# l298.net
KiCad netlist of a schematic drawn in EAGLE
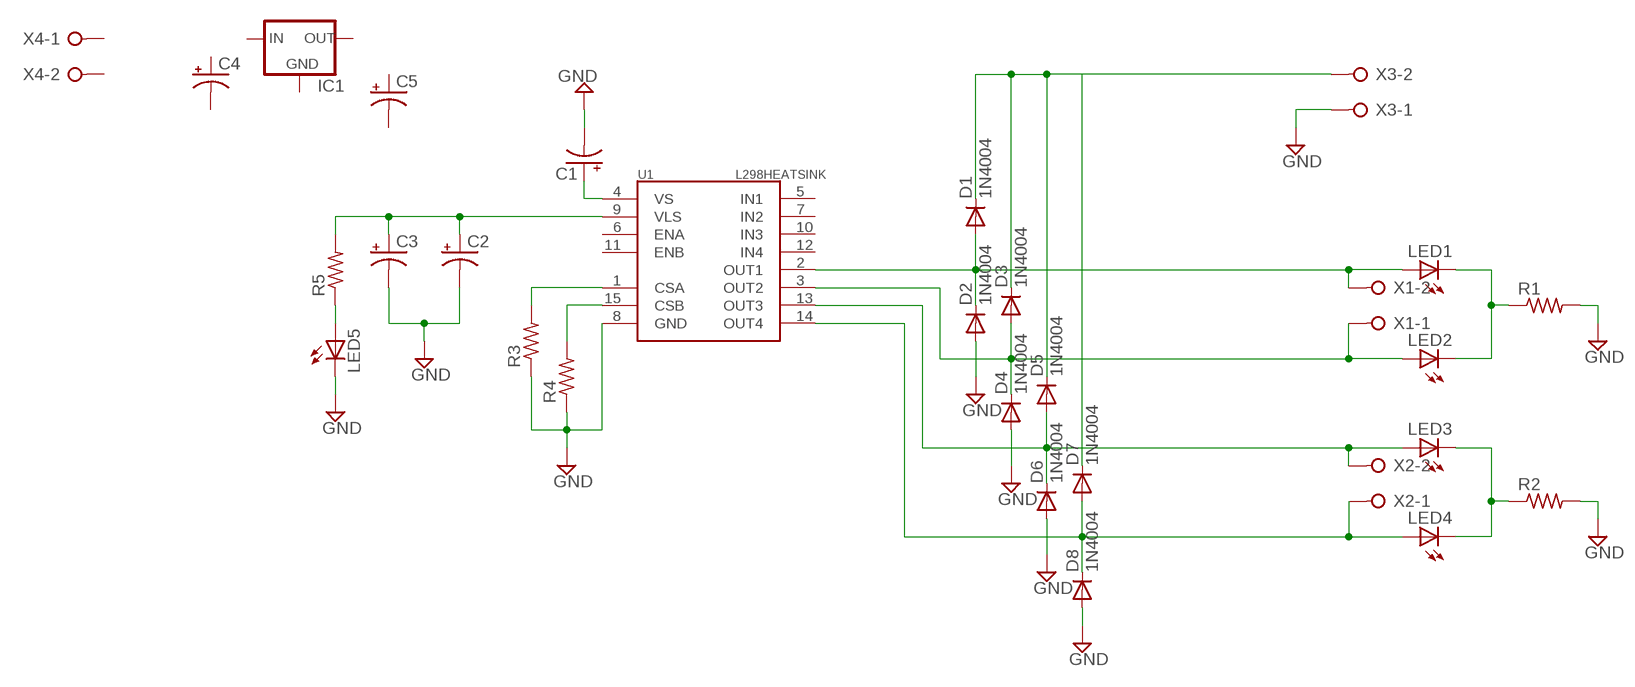
[diagram p0: schematic, sheet 1]

(export (version "E")
  (design (tool "Eeschema 10.0.6"))
  (components
    (comp (ref "C1")
      (value "CPOL-USE3.5-8")
      (footprint "eagle-import:E3,5-8")
      (libsource (lib "eagle-import") (part "CPOL-USE3.5-8"))
    )
    (comp (ref "C2")
      (value "CPOL-USE3.5-8")
      (footprint "eagle-import:E3,5-8")
      (libsource (lib "eagle-import") (part "CPOL-USE3.5-8"))
    )
    (comp (ref "C3")
      (value "CPOL-USE3.5-8")
      (footprint "eagle-import:E3,5-8")
      (libsource (lib "eagle-import") (part "CPOL-USE3.5-8"))
    )
    (comp (ref "C4")
      (value "CPOL-USE3.5-8")
      (footprint "eagle-import:E3,5-8")
      (libsource (lib "eagle-import") (part "CPOL-USE3.5-8"))
    )
    (comp (ref "C5")
      (value "CPOL-USE3.5-8")
      (footprint "eagle-import:E3,5-8")
      (libsource (lib "eagle-import") (part "CPOL-USE3.5-8"))
    )
    (comp (ref "D1")
      (value "1N4004")
      (footprint "eagle-import:DO41-10")
      (libsource (lib "eagle-import") (part "1N4004"))
    )
    (comp (ref "D2")
      (value "1N4004")
      (footprint "eagle-import:DO41-10")
      (libsource (lib "eagle-import") (part "1N4004"))
    )
    (comp (ref "D3")
      (value "1N4004")
      (footprint "eagle-import:DO41-10")
      (libsource (lib "eagle-import") (part "1N4004"))
    )
    (comp (ref "D4")
      (value "1N4004")
      (footprint "eagle-import:DO41-10")
      (libsource (lib "eagle-import") (part "1N4004"))
    )
    (comp (ref "D5")
      (value "1N4004")
      (footprint "eagle-import:DO41-10")
      (libsource (lib "eagle-import") (part "1N4004"))
    )
    (comp (ref "D6")
      (value "1N4004")
      (footprint "eagle-import:DO41-10")
      (libsource (lib "eagle-import") (part "1N4004"))
    )
    (comp (ref "D7")
      (value "1N4004")
      (footprint "eagle-import:DO41-10")
      (libsource (lib "eagle-import") (part "1N4004"))
    )
    (comp (ref "D8")
      (value "1N4004")
      (footprint "eagle-import:DO41-10")
      (libsource (lib "eagle-import") (part "1N4004"))
    )
    (comp (ref "IC1")
      (value "V_REG_78XXSIDE")
      (footprint "eagle-import:78XXL")
      (libsource (lib "eagle-import") (part "V_REG_78XXSIDE"))
    )
    (comp (ref "LED1")
      (value "LED5MM")
      (footprint "eagle-import:LED5MM")
      (libsource (lib "eagle-import") (part "LED5MM"))
    )
    (comp (ref "LED2")
      (value "LED5MM")
      (footprint "eagle-import:LED5MM")
      (libsource (lib "eagle-import") (part "LED5MM"))
    )
    (comp (ref "LED3")
      (value "LED5MM")
      (footprint "eagle-import:LED5MM")
      (libsource (lib "eagle-import") (part "LED5MM"))
    )
    (comp (ref "LED4")
      (value "LED5MM")
      (footprint "eagle-import:LED5MM")
      (libsource (lib "eagle-import") (part "LED5MM"))
    )
    (comp (ref "LED5")
      (value "LED5MM")
      (footprint "eagle-import:LED5MM")
      (libsource (lib "eagle-import") (part "LED5MM"))
    )
    (comp (ref "R1")
      (value "R-US_0207/10")
      (footprint "eagle-import:0207_10")
      (libsource (lib "eagle-import") (part "R-US_0207/10"))
    )
    (comp (ref "R2")
      (value "R-US_0207/10")
      (footprint "eagle-import:0207_10")
      (libsource (lib "eagle-import") (part "R-US_0207/10"))
    )
    (comp (ref "R3")
      (value "R-US_0207/10")
      (footprint "eagle-import:0207_10")
      (libsource (lib "eagle-import") (part "R-US_0207/10"))
    )
    (comp (ref "R4")
      (value "R-US_0207/10")
      (footprint "eagle-import:0207_10")
      (libsource (lib "eagle-import") (part "R-US_0207/10"))
    )
    (comp (ref "R5")
      (value "R-US_0207/10")
      (footprint "eagle-import:0207_10")
      (libsource (lib "eagle-import") (part "R-US_0207/10"))
    )
    (comp (ref "U1")
      (value "L298HEATSINK")
      (footprint "eagle-import:MULTIWATT15_6400BGHEATSINK")
      (libsource (lib "eagle-import") (part "L298HEATSINK"))
    )
    (comp (ref "X1")
      (value "W237-2N")
      (footprint "eagle-import:W237-2N")
      (libsource (lib "eagle-import") (part "W237-2N"))
    )
    (comp (ref "X2")
      (value "W237-2N")
      (footprint "eagle-import:W237-2N")
      (libsource (lib "eagle-import") (part "W237-2N"))
    )
    (comp (ref "X3")
      (value "W237-2N")
      (footprint "eagle-import:W237-2N")
      (libsource (lib "eagle-import") (part "W237-2N"))
    )
    (comp (ref "X4")
      (value "W237-2N")
      (footprint "eagle-import:W237-2N")
      (libsource (lib "eagle-import") (part "W237-2N"))
    )
  )
  (nets
    (net (code "1") (name "GND") (class "Default")
      (node (ref "C1") (pin "-") (pinfunction "-_-") (pintype "passive"))
      (node (ref "C2") (pin "-") (pinfunction "-_-") (pintype "passive"))
      (node (ref "C3") (pin "-") (pinfunction "-_-") (pintype "passive"))
      (node (ref "D2") (pin "A") (pinfunction "A_A") (pintype "passive"))
      (node (ref "D4") (pin "A") (pinfunction "A_A") (pintype "passive"))
      (node (ref "D6") (pin "A") (pinfunction "A_A") (pintype "passive"))
      (node (ref "D8") (pin "A") (pinfunction "A_A") (pintype "passive"))
      (node (ref "LED5") (pin "K") (pinfunction "C_K") (pintype "passive"))
      (node (ref "R1") (pin "2") (pinfunction "2_2") (pintype "passive"))
      (node (ref "R2") (pin "2") (pinfunction "2_2") (pintype "passive"))
      (node (ref "R3") (pin "1") (pinfunction "1_1") (pintype "passive"))
      (node (ref "R4") (pin "1") (pinfunction "1_1") (pintype "passive"))
      (node (ref "U1") (pin "8") (pinfunction "GND_8") (pintype "bidirectional"))
      (node (ref "X3") (pin "1") (pinfunction "KL_1") (pintype "passive"))
    )
    (net (code "2") (name "Net-(LED1-C)") (class "Default")
      (node (ref "LED1") (pin "K") (pinfunction "C_K") (pintype "passive"))
      (node (ref "LED2") (pin "K") (pinfunction "C_K") (pintype "passive"))
      (node (ref "R1") (pin "1") (pinfunction "1_1") (pintype "passive"))
    )
    (net (code "3") (name "Net-(LED3-C)") (class "Default")
      (node (ref "LED3") (pin "K") (pinfunction "C_K") (pintype "passive"))
      (node (ref "LED4") (pin "K") (pinfunction "C_K") (pintype "passive"))
      (node (ref "R2") (pin "1") (pinfunction "1_1") (pintype "passive"))
    )
    (net (code "4") (name "Net-(LED5-PadA)") (class "Default")
      (node (ref "LED5") (pin "A") (pinfunction "A_A") (pintype "passive"))
      (node (ref "R5") (pin "1") (pinfunction "1_1") (pintype "passive"))
    )
    (net (code "5") (name "Net-(U1-CSA)") (class "Default")
      (node (ref "R3") (pin "2") (pinfunction "2_2") (pintype "passive"))
      (node (ref "U1") (pin "1") (pinfunction "CSA_1") (pintype "bidirectional"))
    )
    (net (code "6") (name "Net-(U1-CSB)") (class "Default")
      (node (ref "R4") (pin "2") (pinfunction "2_2") (pintype "passive"))
      (node (ref "U1") (pin "15") (pinfunction "CSB_15") (pintype "bidirectional"))
    )
    (net (code "7") (name "Net-(U1-OUT1)") (class "Default")
      (node (ref "D1") (pin "A") (pinfunction "A_A") (pintype "passive"))
      (node (ref "D2") (pin "C") (pinfunction "C_C") (pintype "passive"))
      (node (ref "LED1") (pin "A") (pinfunction "A_A") (pintype "passive"))
      (node (ref "U1") (pin "2") (pinfunction "OUT1_2") (pintype "bidirectional"))
      (node (ref "X1") (pin "2") (pinfunction "KL_2") (pintype "passive"))
    )
    (net (code "8") (name "Net-(U1-OUT2)") (class "Default")
      (node (ref "D3") (pin "A") (pinfunction "A_A") (pintype "passive"))
      (node (ref "D4") (pin "C") (pinfunction "C_C") (pintype "passive"))
      (node (ref "LED2") (pin "A") (pinfunction "A_A") (pintype "passive"))
      (node (ref "U1") (pin "3") (pinfunction "OUT2_3") (pintype "bidirectional"))
      (node (ref "X1") (pin "1") (pinfunction "KL_1") (pintype "passive"))
    )
    (net (code "9") (name "Net-(U1-OUT3)") (class "Default")
      (node (ref "D5") (pin "A") (pinfunction "A_A") (pintype "passive"))
      (node (ref "D6") (pin "C") (pinfunction "C_C") (pintype "passive"))
      (node (ref "LED3") (pin "A") (pinfunction "A_A") (pintype "passive"))
      (node (ref "U1") (pin "13") (pinfunction "OUT3_13") (pintype "bidirectional"))
      (node (ref "X2") (pin "2") (pinfunction "KL_2") (pintype "passive"))
    )
    (net (code "10") (name "Net-(U1-OUT4)") (class "Default")
      (node (ref "D7") (pin "A") (pinfunction "A_A") (pintype "passive"))
      (node (ref "D8") (pin "C") (pinfunction "C_C") (pintype "passive"))
      (node (ref "LED4") (pin "A") (pinfunction "A_A") (pintype "passive"))
      (node (ref "U1") (pin "14") (pinfunction "OUT4_14") (pintype "bidirectional"))
      (node (ref "X2") (pin "1") (pinfunction "KL_1") (pintype "passive"))
    )
    (net (code "11") (name "Net-(U1-VLS)") (class "Default")
      (node (ref "C2") (pin "+") (pinfunction "+_+") (pintype "passive"))
      (node (ref "C3") (pin "+") (pinfunction "+_+") (pintype "passive"))
      (node (ref "R5") (pin "2") (pinfunction "2_2") (pintype "passive"))
      (node (ref "U1") (pin "9") (pinfunction "VLS_9") (pintype "bidirectional"))
    )
    (net (code "12") (name "Net-(U1-VS)") (class "Default")
      (node (ref "C1") (pin "+") (pinfunction "+_+") (pintype "passive"))
      (node (ref "U1") (pin "4") (pinfunction "VS_4") (pintype "bidirectional"))
    )
    (net (code "13") (name "Net-(X3B-KL)") (class "Default")
      (node (ref "D1") (pin "C") (pinfunction "C_C") (pintype "passive"))
      (node (ref "D3") (pin "C") (pinfunction "C_C") (pintype "passive"))
      (node (ref "D5") (pin "C") (pinfunction "C_C") (pintype "passive"))
      (node (ref "D7") (pin "C") (pinfunction "C_C") (pintype "passive"))
      (node (ref "X3") (pin "2") (pinfunction "KL_2") (pintype "passive"))
    )
    (net (code "14") (name "unconnected-(C4-Pad+)") (class "Default")
      (node (ref "C4") (pin "+") (pinfunction "+_+") (pintype "passive"))
    )
    (net (code "15") (name "unconnected-(C4-Pad-)") (class "Default")
      (node (ref "C4") (pin "-") (pinfunction "-_-") (pintype "passive"))
    )
    (net (code "16") (name "unconnected-(C5-Pad+)") (class "Default")
      (node (ref "C5") (pin "+") (pinfunction "+_+") (pintype "passive"))
    )
    (net (code "17") (name "unconnected-(C5-Pad-)") (class "Default")
      (node (ref "C5") (pin "-") (pinfunction "-_-") (pintype "passive"))
    )
    (net (code "18") (name "unconnected-(IC1-PadGND)") (class "Default")
      (node (ref "IC1") (pin "GND") (pinfunction "GND_GND") (pintype "input"))
    )
    (net (code "19") (name "unconnected-(IC1-PadIN)") (class "Default")
      (node (ref "IC1") (pin "IN") (pinfunction "IN_IN") (pintype "input"))
    )
    (net (code "20") (name "unconnected-(IC1-PadOUT)") (class "Default")
      (node (ref "IC1") (pin "OUT") (pinfunction "OUT_OUT") (pintype "output"))
    )
    (net (code "21") (name "unconnected-(U1-ENA-Pad6)") (class "Default")
      (node (ref "U1") (pin "6") (pinfunction "ENA_6") (pintype "bidirectional"))
    )
    (net (code "22") (name "unconnected-(U1-ENB-Pad11)") (class "Default")
      (node (ref "U1") (pin "11") (pinfunction "ENB_11") (pintype "bidirectional"))
    )
    (net (code "23") (name "unconnected-(U1-IN1-Pad5)") (class "Default")
      (node (ref "U1") (pin "5") (pinfunction "IN1_5") (pintype "bidirectional"))
    )
    (net (code "24") (name "unconnected-(U1-IN2-Pad7)") (class "Default")
      (node (ref "U1") (pin "7") (pinfunction "IN2_7") (pintype "bidirectional"))
    )
    (net (code "25") (name "unconnected-(U1-IN3-Pad10)") (class "Default")
      (node (ref "U1") (pin "10") (pinfunction "IN3_10") (pintype "bidirectional"))
    )
    (net (code "26") (name "unconnected-(U1-IN4-Pad12)") (class "Default")
      (node (ref "U1") (pin "12") (pinfunction "IN4_12") (pintype "bidirectional"))
    )
    (net (code "27") (name "unconnected-(X4A-KL-Pad1)") (class "Default")
      (node (ref "X4") (pin "1") (pinfunction "KL_1") (pintype "passive"))
    )
    (net (code "28") (name "unconnected-(X4B-KL-Pad2)") (class "Default")
      (node (ref "X4") (pin "2") (pinfunction "KL_2") (pintype "passive"))
    )
  )
)
